# wireless_temp_sens.net
KiCad netlist of a schematic drawn in EAGLE
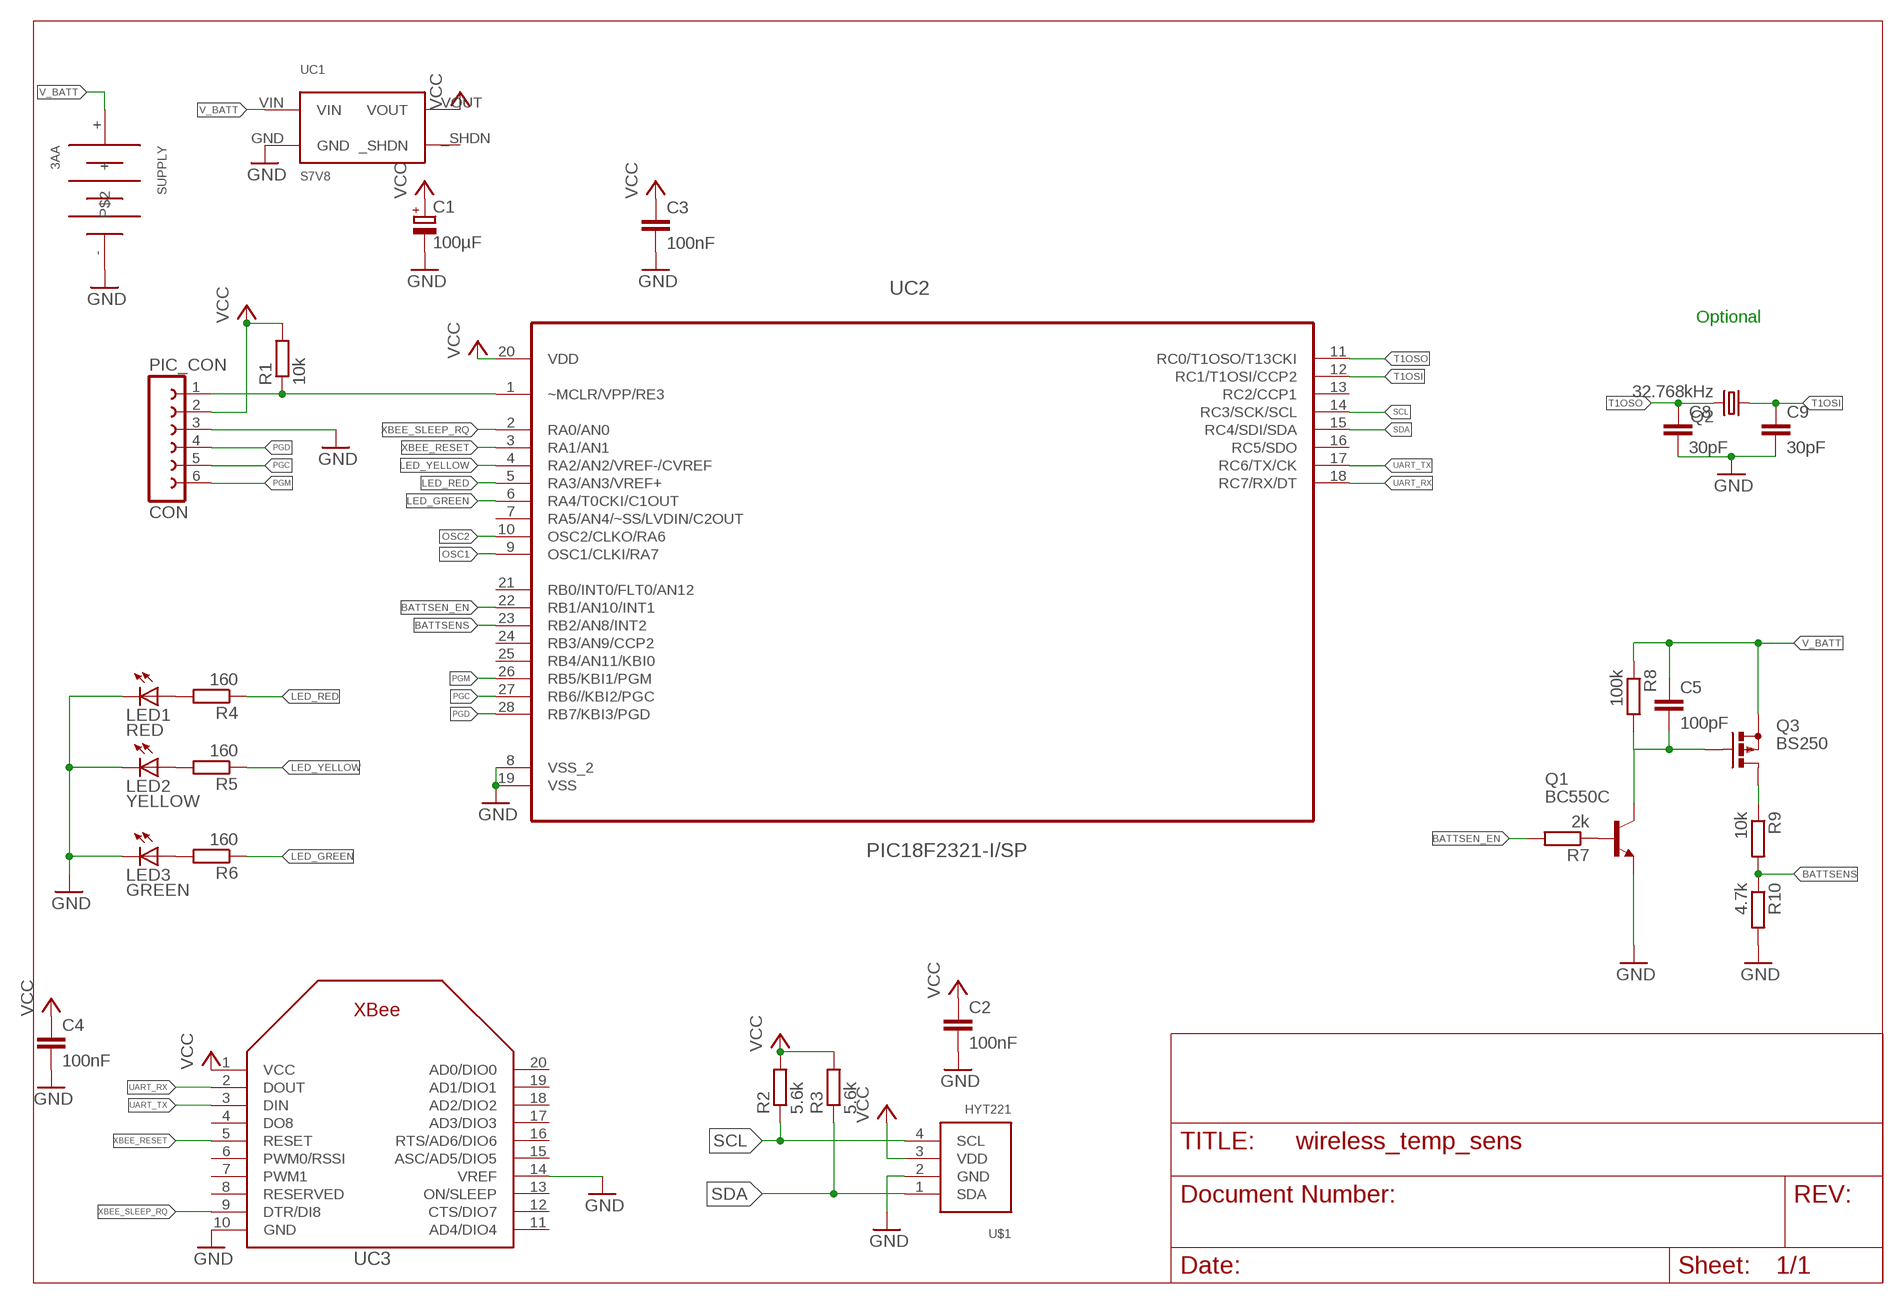
[diagram p0: schematic, sheet 1]

(export (version "E")
  (design (tool "Eeschema 10.0.6"))
  (components
    (comp (ref "C1")
      (value "100µF")
      (footprint "eagle-import:E2,5-6")
      (libsource (lib "eagle-import") (part "CPOL-EUE2.5-6"))
    )
    (comp (ref "C2")
      (value "100nF")
      (footprint "eagle-import:C025-025X050")
      (libsource (lib "eagle-import") (part "C-EU025-025X050"))
    )
    (comp (ref "C3")
      (value "100nF")
      (footprint "eagle-import:C025-025X050")
      (libsource (lib "eagle-import") (part "C-EU025-025X050"))
    )
    (comp (ref "C4")
      (value "100nF")
      (footprint "eagle-import:C025-025X050")
      (libsource (lib "eagle-import") (part "C-EU025-025X050"))
    )
    (comp (ref "C5")
      (value "100pF")
      (footprint "eagle-import:C025-025X050")
      (libsource (lib "eagle-import") (part "C-EU025-025X050"))
    )
    (comp (ref "C8")
      (value "30pF")
      (footprint "eagle-import:C025-024X044")
      (libsource (lib "eagle-import") (part "C-EU025-024X044"))
    )
    (comp (ref "C9")
      (value "30pF")
      (footprint "eagle-import:C025-024X044")
      (libsource (lib "eagle-import") (part "C-EU025-024X044"))
    )
    (comp (ref "CON")
      (value "PIC_CON")
      (footprint "eagle-import:FE06")
      (libsource (lib "eagle-import") (part "FE06-1"))
    )
    (comp (ref "LED1")
      (value "RED")
      (footprint "eagle-import:LED3MM")
      (libsource (lib "eagle-import") (part "LED3MM"))
    )
    (comp (ref "LED2")
      (value "YELLOW")
      (footprint "eagle-import:LED3MM")
      (libsource (lib "eagle-import") (part "LED3MM"))
    )
    (comp (ref "LED3")
      (value "GREEN")
      (footprint "eagle-import:LED3MM")
      (libsource (lib "eagle-import") (part "LED3MM"))
    )
    (comp (ref "Q1")
      (value "BC550C")
      (footprint "eagle-import:TO92-EBC")
      (libsource (lib "eagle-import") (part "BC550C"))
    )
    (comp (ref "Q2")
      (value "32.768kHz")
      (footprint "eagle-import:TC26H")
      (libsource (lib "eagle-import") (part "CRYSTALTC26H"))
    )
    (comp (ref "Q3")
      (value "BS250")
      (footprint "eagle-import:SOT54E")
      (libsource (lib "eagle-import") (part "BS250"))
    )
    (comp (ref "R1")
      (value "10k")
      (footprint "eagle-import:0204_7")
      (libsource (lib "eagle-import") (part "R-EU_0204/7"))
    )
    (comp (ref "R2")
      (value "5.6k")
      (footprint "eagle-import:0204_7")
      (libsource (lib "eagle-import") (part "R-EU_0204/7"))
    )
    (comp (ref "R3")
      (value "5.6k")
      (footprint "eagle-import:0204_7")
      (libsource (lib "eagle-import") (part "R-EU_0204/7"))
    )
    (comp (ref "R4")
      (value "160")
      (footprint "eagle-import:0204_7")
      (libsource (lib "eagle-import") (part "R-EU_0204/7"))
    )
    (comp (ref "R5")
      (value "160")
      (footprint "eagle-import:0204_7")
      (libsource (lib "eagle-import") (part "R-EU_0204/7"))
    )
    (comp (ref "R6")
      (value "160")
      (footprint "eagle-import:0204_7")
      (libsource (lib "eagle-import") (part "R-EU_0204/7"))
    )
    (comp (ref "R7")
      (value "2k")
      (footprint "eagle-import:0204_7")
      (libsource (lib "eagle-import") (part "R-EU_0204/7"))
    )
    (comp (ref "R8")
      (value "100k")
      (footprint "eagle-import:0204_7")
      (libsource (lib "eagle-import") (part "R-EU_0204/7"))
    )
    (comp (ref "R9")
      (value "10k")
      (footprint "eagle-import:0204_7")
      (libsource (lib "eagle-import") (part "R-EU_0204/7"))
    )
    (comp (ref "R10")
      (value "4.7k")
      (footprint "eagle-import:0204_7")
      (libsource (lib "eagle-import") (part "R-EU_0204/7"))
    )
    (comp (ref "SUPPLY")
      (value "3AA")
      (footprint "eagle-import:LR6-R6-R6P")
      (libsource (lib "eagle-import") (part "3AA"))
    )
    (comp (ref "U$1")
      (value "HYT221HYT221-CON")
      (footprint "eagle-import:HYT221-CON")
      (libsource (lib "eagle-import") (part "HYT221HYT221-CON"))
    )
    (comp (ref "UC1")
      (value "S7V8")
      (footprint "eagle-import:S7V8_P")
      (libsource (lib "eagle-import") (part "S7V8"))
    )
    (comp (ref "UC2")
      (value "PIC18F2321-I/SP")
      (footprint "eagle-import:DIP254P762X508-28")
      (libsource (lib "eagle-import") (part "PIC18F2321-I/SP"))
    )
    (comp (ref "UC3")
      (value "XBEE")
      (footprint "eagle-import:XBEE")
      (libsource (lib "eagle-import") (part "XBEE"))
    )
  )
  (nets
    (net (code "1") (name "BATTSENS") (class "Default")
      (node (ref "R10") (pin "1") (pinfunction "1_1") (pintype "passive"))
      (node (ref "R9") (pin "2") (pinfunction "2_2") (pintype "passive"))
      (node (ref "UC2") (pin "23") (pinfunction "RB2/AN8/INT2_23") (pintype "bidirectional"))
    )
    (net (code "2") (name "BATTSEN_EN") (class "Default")
      (node (ref "R7") (pin "2") (pinfunction "2_2") (pintype "passive"))
      (node (ref "UC2") (pin "22") (pinfunction "RB1/AN10/INT1_22") (pintype "bidirectional"))
    )
    (net (code "3") (name "GND") (class "Default")
      (node (ref "C1") (pin "-") (pinfunction "-_-") (pintype "passive"))
      (node (ref "C2") (pin "2") (pinfunction "2_2") (pintype "passive"))
      (node (ref "C3") (pin "2") (pinfunction "2_2") (pintype "passive"))
      (node (ref "C4") (pin "2") (pinfunction "2_2") (pintype "passive"))
      (node (ref "C8") (pin "2") (pinfunction "2_2") (pintype "passive"))
      (node (ref "C9") (pin "2") (pinfunction "2_2") (pintype "passive"))
      (node (ref "CON") (pin "3") (pinfunction "3_3") (pintype "passive"))
      (node (ref "LED1") (pin "K") (pinfunction "C_K") (pintype "passive"))
      (node (ref "LED2") (pin "K") (pinfunction "C_K") (pintype "passive"))
      (node (ref "LED3") (pin "K") (pinfunction "C_K") (pintype "passive"))
      (node (ref "Q1") (pin "E") (pinfunction "E_E") (pintype "passive"))
      (node (ref "R10") (pin "2") (pinfunction "2_2") (pintype "passive"))
      (node (ref "SUPPLY") (pin "-") (pinfunction "P$2_-") (pintype "output"))
      (node (ref "U$1") (pin "2") (pinfunction "GND_2") (pintype "power_in"))
      (node (ref "UC1") (pin "GND") (pinfunction "GND_GND") (pintype "bidirectional"))
      (node (ref "UC2") (pin "19") (pinfunction "VSS_19") (pintype "passive"))
      (node (ref "UC2") (pin "8") (pinfunction "VSS_2_8") (pintype "passive"))
      (node (ref "UC3") (pin "10") (pinfunction "GND_10") (pintype "power_in"))
      (node (ref "UC3") (pin "14") (pinfunction "VREF_14") (pintype "input"))
    )
    (net (code "4") (name "LED_GREEN") (class "Default")
      (node (ref "R6") (pin "1") (pinfunction "1_1") (pintype "passive"))
      (node (ref "UC2") (pin "6") (pinfunction "RA4/T0CKI/C1OUT_6") (pintype "bidirectional"))
    )
    (net (code "5") (name "LED_RED") (class "Default")
      (node (ref "R4") (pin "1") (pinfunction "1_1") (pintype "passive"))
      (node (ref "UC2") (pin "5") (pinfunction "RA3/AN3/VREF+_5") (pintype "bidirectional"))
    )
    (net (code "6") (name "LED_YELLOW") (class "Default")
      (node (ref "R5") (pin "1") (pinfunction "1_1") (pintype "passive"))
      (node (ref "UC2") (pin "4") (pinfunction "RA2/AN2/VREF-/CVREF_4") (pintype "bidirectional"))
    )
    (net (code "7") (name "Net-(C5-Pad2)") (class "Default")
      (node (ref "C5") (pin "2") (pinfunction "2_2") (pintype "passive"))
      (node (ref "Q1") (pin "C") (pinfunction "C_C") (pintype "passive"))
      (node (ref "Q3") (pin "G") (pinfunction "G_G") (pintype "passive"))
      (node (ref "R8") (pin "2") (pinfunction "2_2") (pintype "passive"))
    )
    (net (code "8") (name "Net-(LED1-PadA)") (class "Default")
      (node (ref "LED1") (pin "A") (pinfunction "A_A") (pintype "passive"))
      (node (ref "R4") (pin "2") (pinfunction "2_2") (pintype "passive"))
    )
    (net (code "9") (name "Net-(LED2-PadA)") (class "Default")
      (node (ref "LED2") (pin "A") (pinfunction "A_A") (pintype "passive"))
      (node (ref "R5") (pin "2") (pinfunction "2_2") (pintype "passive"))
    )
    (net (code "10") (name "Net-(LED3-PadA)") (class "Default")
      (node (ref "LED3") (pin "A") (pinfunction "A_A") (pintype "passive"))
      (node (ref "R6") (pin "2") (pinfunction "2_2") (pintype "passive"))
    )
    (net (code "11") (name "Net-(Q1-PadB)") (class "Default")
      (node (ref "Q1") (pin "B") (pinfunction "B_B") (pintype "passive"))
      (node (ref "R7") (pin "1") (pinfunction "1_1") (pintype "passive"))
    )
    (net (code "12") (name "Net-(Q3-PadD)") (class "Default")
      (node (ref "Q3") (pin "D") (pinfunction "D_D") (pintype "passive"))
      (node (ref "R9") (pin "1") (pinfunction "1_1") (pintype "passive"))
    )
    (net (code "13") (name "Net-(UC2-~{MCLR{slash}VPP{slash}RE3})") (class "Default")
      (node (ref "CON") (pin "1") (pinfunction "1_1") (pintype "passive"))
      (node (ref "R1") (pin "1") (pinfunction "1_1") (pintype "passive"))
      (node (ref "UC2") (pin "1") (pinfunction "~{MCLR/VPP/RE3}_1") (pintype "input"))
    )
    (net (code "14") (name "OSC1") (class "Default")
      (node (ref "UC2") (pin "9") (pinfunction "OSC1/CLKI/RA7_9") (pintype "bidirectional"))
    )
    (net (code "15") (name "OSC2") (class "Default")
      (node (ref "UC2") (pin "10") (pinfunction "OSC2/CLKO/RA6_10") (pintype "bidirectional"))
    )
    (net (code "16") (name "PGC") (class "Default")
      (node (ref "CON") (pin "5") (pinfunction "5_5") (pintype "passive"))
      (node (ref "UC2") (pin "27") (pinfunction "RB6//KBI2/PGC_27") (pintype "bidirectional"))
    )
    (net (code "17") (name "PGD") (class "Default")
      (node (ref "CON") (pin "4") (pinfunction "4_4") (pintype "passive"))
      (node (ref "UC2") (pin "28") (pinfunction "RB7/KBI3/PGD_28") (pintype "bidirectional"))
    )
    (net (code "18") (name "PGM") (class "Default")
      (node (ref "CON") (pin "6") (pinfunction "6_6") (pintype "passive"))
      (node (ref "UC2") (pin "26") (pinfunction "RB5/KBI1/PGM_26") (pintype "bidirectional"))
    )
    (net (code "19") (name "SCL") (class "Default")
      (node (ref "R2") (pin "1") (pinfunction "1_1") (pintype "passive"))
      (node (ref "U$1") (pin "4") (pinfunction "SCL_4") (pintype "input"))
      (node (ref "UC2") (pin "14") (pinfunction "RC3/SCK/SCL_14") (pintype "bidirectional"))
    )
    (net (code "20") (name "SDA") (class "Default")
      (node (ref "R3") (pin "1") (pinfunction "1_1") (pintype "passive"))
      (node (ref "U$1") (pin "1") (pinfunction "SDA_1") (pintype "bidirectional"))
      (node (ref "UC2") (pin "15") (pinfunction "RC4/SDI/SDA_15") (pintype "bidirectional"))
    )
    (net (code "21") (name "T1OSI") (class "Default")
      (node (ref "C9") (pin "1") (pinfunction "1_1") (pintype "passive"))
      (node (ref "Q2") (pin "1") (pinfunction "1_1") (pintype "passive"))
      (node (ref "UC2") (pin "12") (pinfunction "RC1/T1OSI/CCP2_12") (pintype "bidirectional"))
    )
    (net (code "22") (name "T1OSO") (class "Default")
      (node (ref "C8") (pin "1") (pinfunction "1_1") (pintype "passive"))
      (node (ref "Q2") (pin "2") (pinfunction "2_2") (pintype "passive"))
      (node (ref "UC2") (pin "11") (pinfunction "RC0/T1OSO/T13CKI_11") (pintype "bidirectional"))
    )
    (net (code "23") (name "UART_RX") (class "Default")
      (node (ref "UC2") (pin "18") (pinfunction "RC7/RX/DT_18") (pintype "bidirectional"))
      (node (ref "UC3") (pin "2") (pinfunction "DOUT_2") (pintype "output"))
    )
    (net (code "24") (name "UART_TX") (class "Default")
      (node (ref "UC2") (pin "17") (pinfunction "RC6/TX/CK_17") (pintype "bidirectional"))
      (node (ref "UC3") (pin "3") (pinfunction "DIN_3") (pintype "input"))
    )
    (net (code "25") (name "VCC") (class "Default")
      (node (ref "C1") (pin "+") (pinfunction "+_+") (pintype "passive"))
      (node (ref "C2") (pin "1") (pinfunction "1_1") (pintype "passive"))
      (node (ref "C3") (pin "1") (pinfunction "1_1") (pintype "passive"))
      (node (ref "C4") (pin "1") (pinfunction "1_1") (pintype "passive"))
      (node (ref "CON") (pin "2") (pinfunction "2_2") (pintype "passive"))
      (node (ref "R1") (pin "2") (pinfunction "2_2") (pintype "passive"))
      (node (ref "R2") (pin "2") (pinfunction "2_2") (pintype "passive"))
      (node (ref "R3") (pin "2") (pinfunction "2_2") (pintype "passive"))
      (node (ref "U$1") (pin "3") (pinfunction "VDD_3") (pintype "power_in"))
      (node (ref "UC1") (pin "VOUT") (pinfunction "VOUT_VOUT") (pintype "power_in"))
      (node (ref "UC2") (pin "20") (pinfunction "VDD_20") (pintype "power_in"))
      (node (ref "UC3") (pin "1") (pinfunction "VCC_1") (pintype "power_in"))
    )
    (net (code "26") (name "V_BATT") (class "Default")
      (node (ref "C5") (pin "1") (pinfunction "1_1") (pintype "passive"))
      (node (ref "Q3") (pin "S") (pinfunction "S_S") (pintype "passive"))
      (node (ref "R8") (pin "1") (pinfunction "1_1") (pintype "passive"))
      (node (ref "SUPPLY") (pin "+") (pinfunction "+_+") (pintype "output"))
      (node (ref "UC1") (pin "VIN") (pinfunction "VIN_VIN") (pintype "input"))
    )
    (net (code "27") (name "XBEE_RESET") (class "Default")
      (node (ref "UC2") (pin "3") (pinfunction "RA1/AN1_3") (pintype "bidirectional"))
      (node (ref "UC3") (pin "5") (pinfunction "RESET_5") (pintype "input"))
    )
    (net (code "28") (name "XBEE_SLEEP_RQ") (class "Default")
      (node (ref "UC2") (pin "2") (pinfunction "RA0/AN0_2") (pintype "bidirectional"))
      (node (ref "UC3") (pin "9") (pinfunction "DTR/DI8_9") (pintype "input"))
    )
    (net (code "29") (name "unconnected-(UC1-Pad_SHDN)") (class "Default")
      (node (ref "UC1") (pin "_SHDN") (pinfunction "_SHDN__SHDN") (pintype "output"))
    )
    (net (code "30") (name "unconnected-(UC2-RA5{slash}AN4{slash}~{SS{slash}LVDIN{slash}C2OUT}-Pad7)") (class "Default")
      (node (ref "UC2") (pin "7") (pinfunction "RA5/AN4/~{SS/LVDIN/C2OUT}_7") (pintype "bidirectional"))
    )
    (net (code "31") (name "unconnected-(UC2-RB0{slash}INT0{slash}FLT0{slash}AN12-Pad21)") (class "Default")
      (node (ref "UC2") (pin "21") (pinfunction "RB0/INT0/FLT0/AN12_21") (pintype "bidirectional"))
    )
    (net (code "32") (name "unconnected-(UC2-RB3{slash}AN9{slash}CCP2-Pad24)") (class "Default")
      (node (ref "UC2") (pin "24") (pinfunction "RB3/AN9/CCP2_24") (pintype "bidirectional"))
    )
    (net (code "33") (name "unconnected-(UC2-RB4{slash}AN11{slash}KBI0-Pad25)") (class "Default")
      (node (ref "UC2") (pin "25") (pinfunction "RB4/AN11/KBI0_25") (pintype "bidirectional"))
    )
    (net (code "34") (name "unconnected-(UC2-RC2{slash}CCP1-Pad13)") (class "Default")
      (node (ref "UC2") (pin "13") (pinfunction "RC2/CCP1_13") (pintype "bidirectional"))
    )
    (net (code "35") (name "unconnected-(UC2-RC5{slash}SDO-Pad16)") (class "Default")
      (node (ref "UC2") (pin "16") (pinfunction "RC5/SDO_16") (pintype "bidirectional"))
    )
    (net (code "36") (name "unconnected-(UC3-AD0{slash}DIO0-Pad20)") (class "Default")
      (node (ref "UC3") (pin "20") (pinfunction "AD0/DIO0_20") (pintype "bidirectional"))
    )
    (net (code "37") (name "unconnected-(UC3-AD1{slash}DIO1-Pad19)") (class "Default")
      (node (ref "UC3") (pin "19") (pinfunction "AD1/DIO1_19") (pintype "bidirectional"))
    )
    (net (code "38") (name "unconnected-(UC3-AD2{slash}DIO2-Pad18)") (class "Default")
      (node (ref "UC3") (pin "18") (pinfunction "AD2/DIO2_18") (pintype "bidirectional"))
    )
    (net (code "39") (name "unconnected-(UC3-AD3{slash}DIO3-Pad17)") (class "Default")
      (node (ref "UC3") (pin "17") (pinfunction "AD3/DIO3_17") (pintype "bidirectional"))
    )
    (net (code "40") (name "unconnected-(UC3-AD4{slash}DIO4-Pad11)") (class "Default")
      (node (ref "UC3") (pin "11") (pinfunction "AD4/DIO4_11") (pintype "bidirectional"))
    )
    (net (code "41") (name "unconnected-(UC3-ASC{slash}AD5{slash}DIO5-Pad15)") (class "Default")
      (node (ref "UC3") (pin "15") (pinfunction "ASC/AD5/DIO5_15") (pintype "bidirectional"))
    )
    (net (code "42") (name "unconnected-(UC3-CTS{slash}DIO7-Pad12)") (class "Default")
      (node (ref "UC3") (pin "12") (pinfunction "CTS/DIO7_12") (pintype "bidirectional"))
    )
    (net (code "43") (name "unconnected-(UC3-DO8-Pad4)") (class "Default")
      (node (ref "UC3") (pin "4") (pinfunction "DO8_4") (pintype "output"))
    )
    (net (code "44") (name "unconnected-(UC3-ON{slash}SLEEP-Pad13)") (class "Default")
      (node (ref "UC3") (pin "13") (pinfunction "ON/SLEEP_13") (pintype "output"))
    )
    (net (code "45") (name "unconnected-(UC3-PWM0{slash}RSSI-Pad6)") (class "Default")
      (node (ref "UC3") (pin "6") (pinfunction "PWM0/RSSI_6") (pintype "output"))
    )
    (net (code "46") (name "unconnected-(UC3-PWM1-Pad7)") (class "Default")
      (node (ref "UC3") (pin "7") (pinfunction "PWM1_7") (pintype "output"))
    )
    (net (code "47") (name "unconnected-(UC3-RESERVED-Pad8)") (class "Default")
      (node (ref "UC3") (pin "8") (pinfunction "RESERVED_8") (pintype "no_connect"))
    )
    (net (code "48") (name "unconnected-(UC3-RTS{slash}AD6{slash}DIO6-Pad16)") (class "Default")
      (node (ref "UC3") (pin "16") (pinfunction "RTS/AD6/DIO6_16") (pintype "bidirectional"))
    )
  )
)
